# Dual_Serial_Card_V2.net
KiCad netlist of a schematic drawn in EAGLE
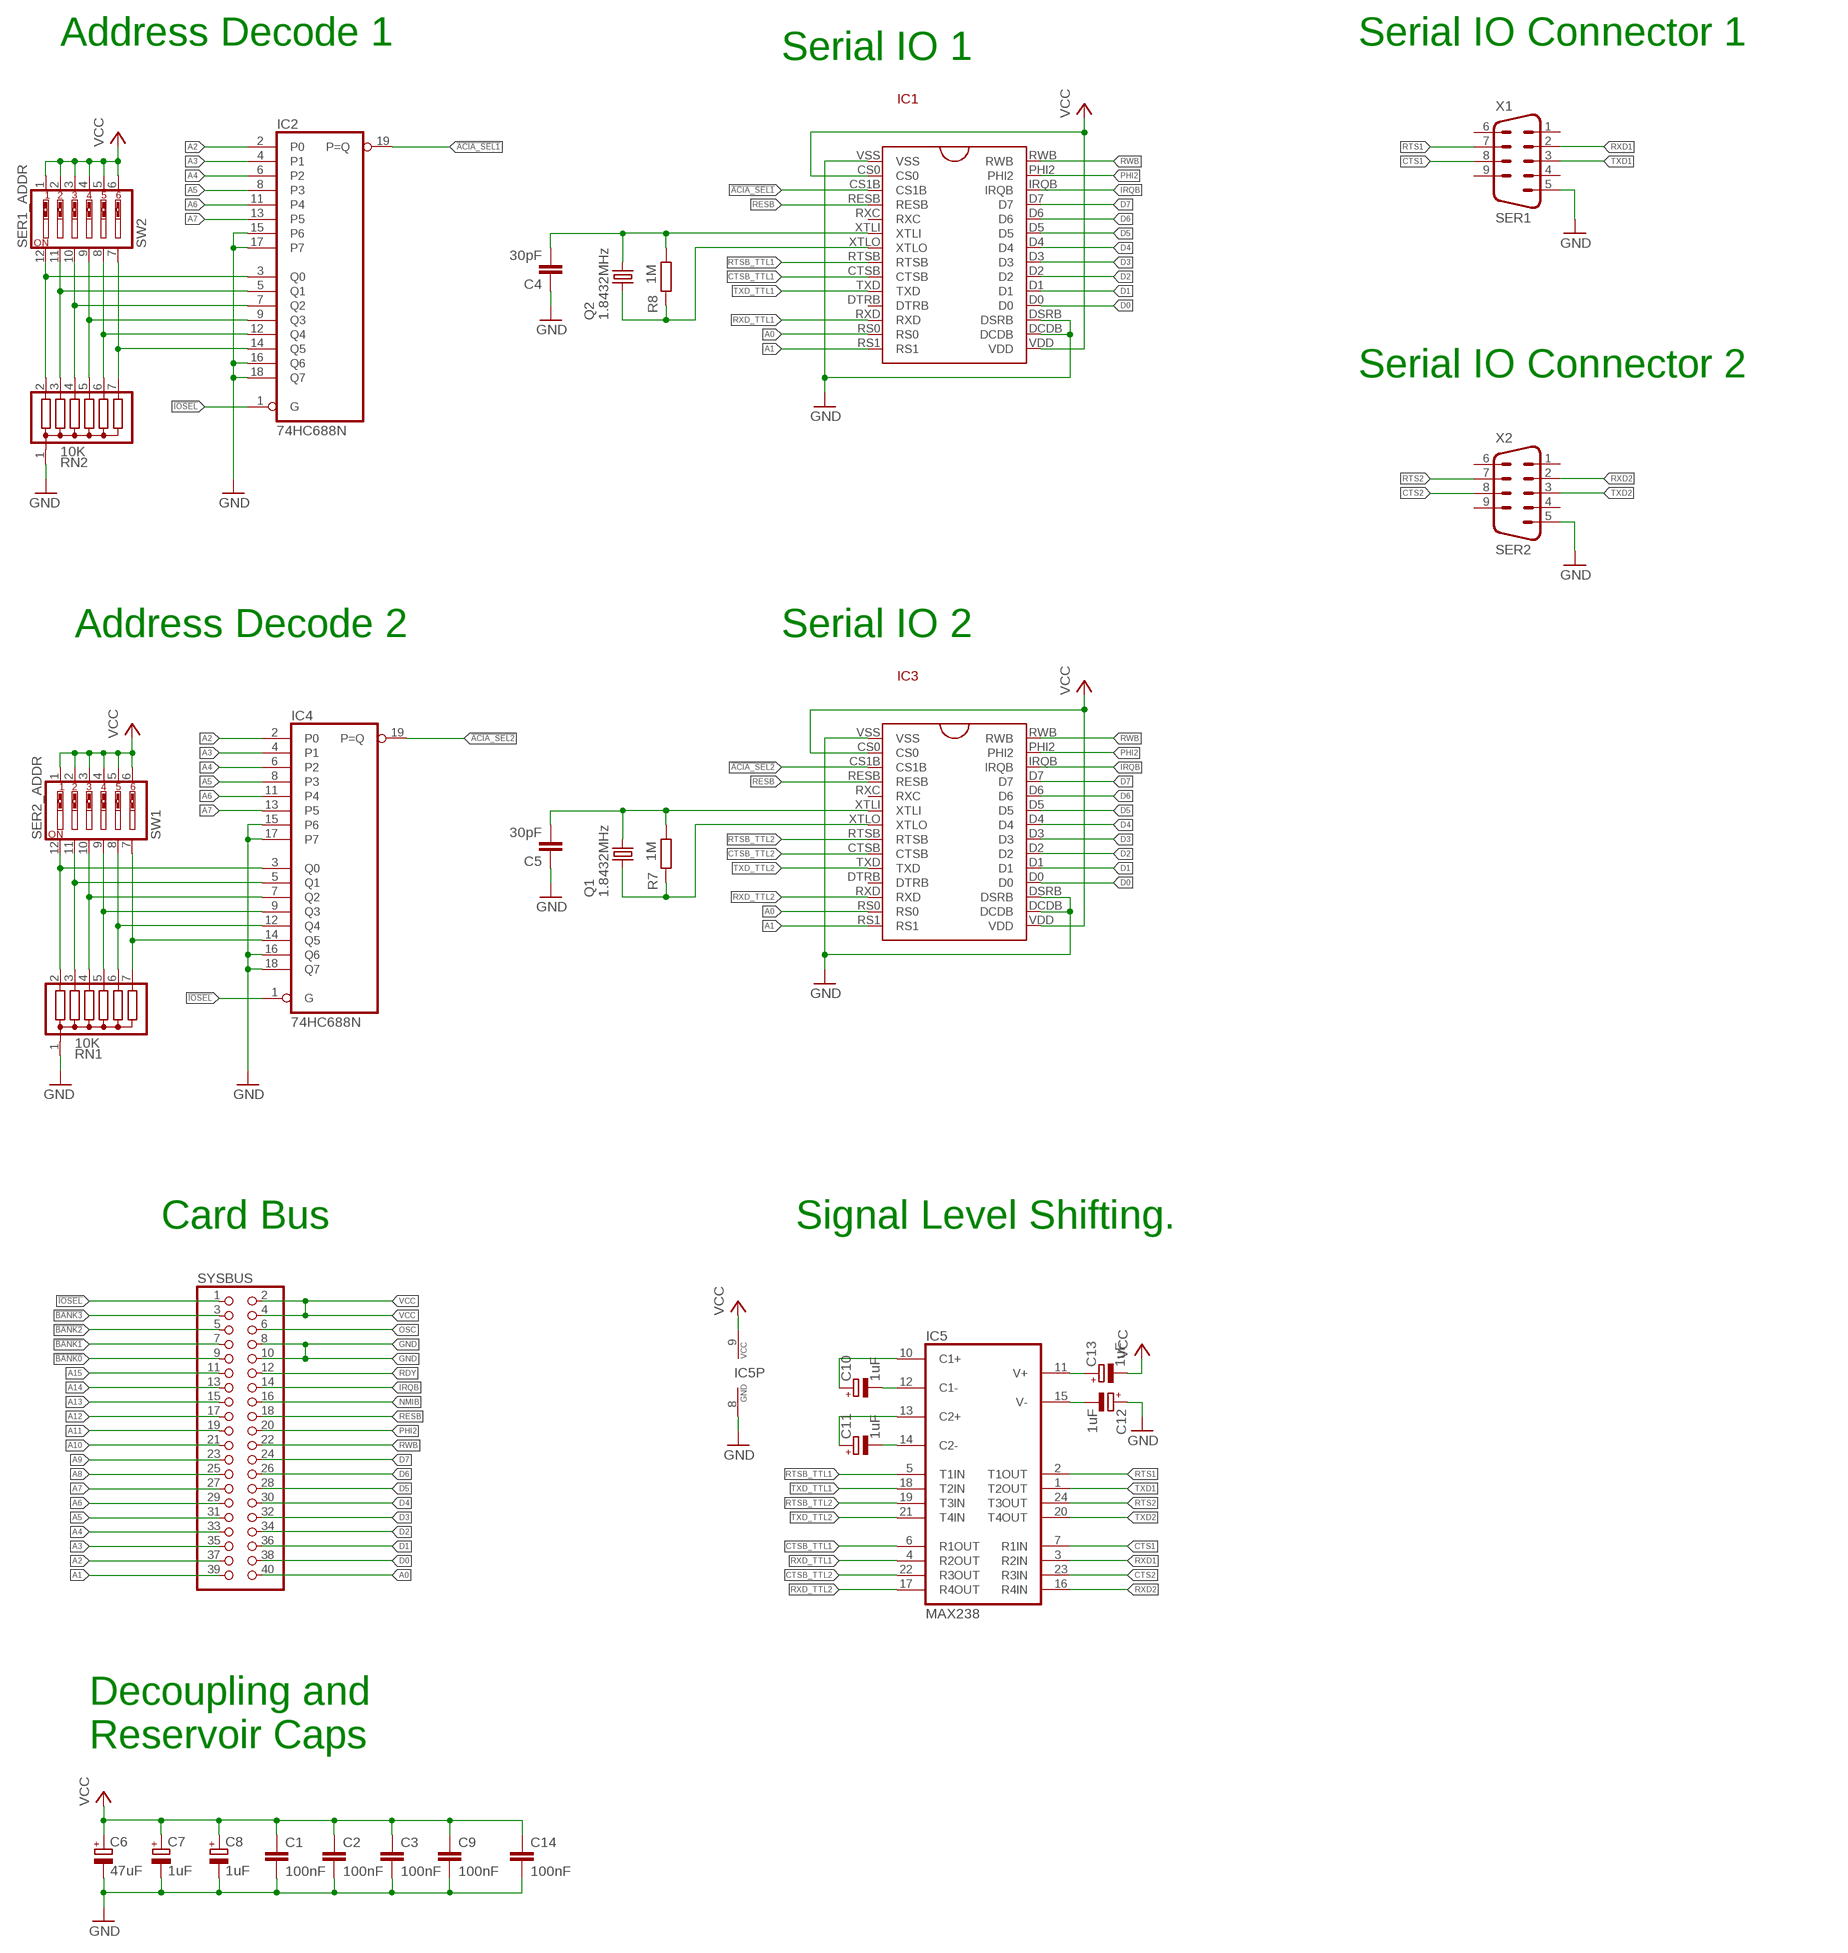
[diagram p0: schematic, sheet 1]

(export (version "E")
  (design (tool "Eeschema 10.0.6"))
  (components
    (comp (ref "C1")
      (value "100nF")
      (footprint "eagle-import:C025-025X050")
      (libsource (lib "eagle-import") (part "C-EU025-025X050"))
    )
    (comp (ref "C2")
      (value "100nF")
      (footprint "eagle-import:C025-025X050")
      (libsource (lib "eagle-import") (part "C-EU025-025X050"))
    )
    (comp (ref "C3")
      (value "100nF")
      (footprint "eagle-import:C025-025X050")
      (libsource (lib "eagle-import") (part "C-EU025-025X050"))
    )
    (comp (ref "C4")
      (value "30pF")
      (footprint "eagle-import:C050-025X075")
      (libsource (lib "eagle-import") (part "C-EU050-025X075"))
    )
    (comp (ref "C5")
      (value "30pF")
      (footprint "eagle-import:C050-025X075")
      (libsource (lib "eagle-import") (part "C-EU050-025X075"))
    )
    (comp (ref "C6")
      (value "47uF")
      (footprint "eagle-import:E2,5-7")
      (libsource (lib "eagle-import") (part "CPOL-EUE2.5-7"))
    )
    (comp (ref "C7")
      (value "1uF")
      (footprint "eagle-import:E2,5-5")
      (libsource (lib "eagle-import") (part "CPOL-EUE2.5-5"))
    )
    (comp (ref "C8")
      (value "1uF")
      (footprint "eagle-import:E2,5-5")
      (libsource (lib "eagle-import") (part "CPOL-EUE2.5-5"))
    )
    (comp (ref "C9")
      (value "100nF")
      (footprint "eagle-import:C025-025X050")
      (libsource (lib "eagle-import") (part "C-EU025-025X050"))
    )
    (comp (ref "C10")
      (value "1uF")
      (footprint "eagle-import:E2,5-5")
      (libsource (lib "eagle-import") (part "CPOL-EUE2.5-5"))
    )
    (comp (ref "C11")
      (value "1uF")
      (footprint "eagle-import:E2,5-5")
      (libsource (lib "eagle-import") (part "CPOL-EUE2.5-5"))
    )
    (comp (ref "C12")
      (value "1uF")
      (footprint "eagle-import:E2,5-5")
      (libsource (lib "eagle-import") (part "CPOL-EUE2.5-5"))
    )
    (comp (ref "C13")
      (value "1uF")
      (footprint "eagle-import:E2,5-5")
      (libsource (lib "eagle-import") (part "CPOL-EUE2.5-5"))
    )
    (comp (ref "C14")
      (value "100nF")
      (footprint "eagle-import:C025-025X050")
      (libsource (lib "eagle-import") (part "C-EU025-025X050"))
    )
    (comp (ref "IC1")
      (value "W65C51N-DIP")
      (footprint "eagle-import:W65C51N-DIP")
      (libsource (lib "eagle-import") (part "W65C51N-DIP"))
    )
    (comp (ref "IC2")
      (value "74HC688N")
      (footprint "eagle-import:DIL20")
      (libsource (lib "eagle-import") (part "74688NHC"))
    )
    (comp (ref "IC3")
      (value "W65C51N-DIP")
      (footprint "eagle-import:W65C51N-DIP")
      (libsource (lib "eagle-import") (part "W65C51N-DIP"))
    )
    (comp (ref "IC4")
      (value "74HC688N")
      (footprint "eagle-import:DIL20")
      (libsource (lib "eagle-import") (part "74688NHC"))
    )
    (comp (ref "IC5")
      (value "MAX238")
      (footprint "eagle-import:DIL24-3")
      (libsource (lib "eagle-import") (part "MAX238"))
    )
    (comp (ref "Q1")
      (value "1.8432MHz")
      (footprint "eagle-import:HC49_S")
      (libsource (lib "eagle-import") (part "CRYSTALHC49S"))
    )
    (comp (ref "Q2")
      (value "1.8432MHz")
      (footprint "eagle-import:HC49_S")
      (libsource (lib "eagle-import") (part "CRYSTALHC49S"))
    )
    (comp (ref "R7")
      (value "1M")
      (footprint "eagle-import:0207_2V")
      (libsource (lib "eagle-import") (part "R-EU_0207/2V"))
    )
    (comp (ref "R8")
      (value "1M")
      (footprint "eagle-import:0207_2V")
      (libsource (lib "eagle-import") (part "R-EU_0207/2V"))
    )
    (comp (ref "RN1")
      (value "10K")
      (footprint "eagle-import:SIL7")
      (libsource (lib "eagle-import") (part "G06R"))
    )
    (comp (ref "RN2")
      (value "10K")
      (footprint "eagle-import:SIL7")
      (libsource (lib "eagle-import") (part "G06R"))
    )
    (comp (ref "SW1")
      (value "SER2_ADDR")
      (footprint "eagle-import:EDG-06")
      (libsource (lib "eagle-import") (part "SW_DIP-6"))
    )
    (comp (ref "SW2")
      (value "SER1_ADDR")
      (footprint "eagle-import:EDG-06")
      (libsource (lib "eagle-import") (part "SW_DIP-6"))
    )
    (comp (ref "SYSBUS")
      (value "PINHD-2X20/90")
      (footprint "eagle-import:2X20_90")
      (libsource (lib "eagle-import") (part "PINHD-2X20/90"))
    )
    (comp (ref "X1")
      (value "SER1")
      (footprint "eagle-import:M09HP")
      (libsource (lib "eagle-import") (part "M09HP"))
    )
    (comp (ref "X2")
      (value "SER2")
      (footprint "eagle-import:M09HP")
      (libsource (lib "eagle-import") (part "M09HP"))
    )
  )
  (nets
    (net (code "1") (name "/~{ACIA_SEL1}") (class "Default")
      (node (ref "IC1") (pin "CS1B") (pinfunction "CS1B_CS1B") (pintype "input"))
      (node (ref "IC2") (pin "19") (pinfunction "P=Q_19") (pintype "output"))
    )
    (net (code "2") (name "/~{ACIA_SEL2}") (class "Default")
      (node (ref "IC3") (pin "CS1B") (pinfunction "CS1B_CS1B") (pintype "input"))
      (node (ref "IC4") (pin "19") (pinfunction "P=Q_19") (pintype "output"))
    )
    (net (code "3") (name "/~{BANK0}") (class "Default")
      (node (ref "SYSBUS") (pin "9") (pinfunction "9_9") (pintype "passive"))
    )
    (net (code "4") (name "/~{BANK1}") (class "Default")
      (node (ref "SYSBUS") (pin "7") (pinfunction "7_7") (pintype "passive"))
    )
    (net (code "5") (name "/~{BANK2}") (class "Default")
      (node (ref "SYSBUS") (pin "5") (pinfunction "5_5") (pintype "passive"))
    )
    (net (code "6") (name "/~{BANK3}") (class "Default")
      (node (ref "SYSBUS") (pin "3") (pinfunction "3_3") (pintype "passive"))
    )
    (net (code "7") (name "/~{IOSEL}") (class "Default")
      (node (ref "IC2") (pin "1") (pinfunction "G_1") (pintype "input"))
      (node (ref "IC4") (pin "1") (pinfunction "G_1") (pintype "input"))
      (node (ref "SYSBUS") (pin "1") (pinfunction "1_1") (pintype "passive"))
    )
    (net (code "8") (name "A0") (class "Default")
      (node (ref "IC1") (pin "RS0") (pinfunction "RS0_RS0") (pintype "input"))
      (node (ref "IC3") (pin "RS0") (pinfunction "RS0_RS0") (pintype "input"))
      (node (ref "SYSBUS") (pin "40") (pinfunction "40_40") (pintype "passive"))
    )
    (net (code "9") (name "A1") (class "Default")
      (node (ref "IC1") (pin "RS1") (pinfunction "RS1_RS1") (pintype "input"))
      (node (ref "IC3") (pin "RS1") (pinfunction "RS1_RS1") (pintype "input"))
      (node (ref "SYSBUS") (pin "39") (pinfunction "39_39") (pintype "passive"))
    )
    (net (code "10") (name "A2") (class "Default")
      (node (ref "IC2") (pin "2") (pinfunction "P0_2") (pintype "input"))
      (node (ref "IC4") (pin "2") (pinfunction "P0_2") (pintype "input"))
      (node (ref "SYSBUS") (pin "37") (pinfunction "37_37") (pintype "passive"))
    )
    (net (code "11") (name "A3") (class "Default")
      (node (ref "IC2") (pin "4") (pinfunction "P1_4") (pintype "input"))
      (node (ref "IC4") (pin "4") (pinfunction "P1_4") (pintype "input"))
      (node (ref "SYSBUS") (pin "35") (pinfunction "35_35") (pintype "passive"))
    )
    (net (code "12") (name "A4") (class "Default")
      (node (ref "IC2") (pin "6") (pinfunction "P2_6") (pintype "input"))
      (node (ref "IC4") (pin "6") (pinfunction "P2_6") (pintype "input"))
      (node (ref "SYSBUS") (pin "33") (pinfunction "33_33") (pintype "passive"))
    )
    (net (code "13") (name "A5") (class "Default")
      (node (ref "IC2") (pin "8") (pinfunction "P3_8") (pintype "input"))
      (node (ref "IC4") (pin "8") (pinfunction "P3_8") (pintype "input"))
      (node (ref "SYSBUS") (pin "31") (pinfunction "31_31") (pintype "passive"))
    )
    (net (code "14") (name "A6") (class "Default")
      (node (ref "IC2") (pin "11") (pinfunction "P4_11") (pintype "input"))
      (node (ref "IC4") (pin "11") (pinfunction "P4_11") (pintype "input"))
      (node (ref "SYSBUS") (pin "29") (pinfunction "29_29") (pintype "passive"))
    )
    (net (code "15") (name "A7") (class "Default")
      (node (ref "IC2") (pin "13") (pinfunction "P5_13") (pintype "input"))
      (node (ref "IC4") (pin "13") (pinfunction "P5_13") (pintype "input"))
      (node (ref "SYSBUS") (pin "27") (pinfunction "27_27") (pintype "passive"))
    )
    (net (code "16") (name "A8") (class "Default")
      (node (ref "SYSBUS") (pin "25") (pinfunction "25_25") (pintype "passive"))
    )
    (net (code "17") (name "A9") (class "Default")
      (node (ref "SYSBUS") (pin "23") (pinfunction "23_23") (pintype "passive"))
    )
    (net (code "18") (name "A10") (class "Default")
      (node (ref "SYSBUS") (pin "21") (pinfunction "21_21") (pintype "passive"))
    )
    (net (code "19") (name "A11") (class "Default")
      (node (ref "SYSBUS") (pin "19") (pinfunction "19_19") (pintype "passive"))
    )
    (net (code "20") (name "A12") (class "Default")
      (node (ref "SYSBUS") (pin "17") (pinfunction "17_17") (pintype "passive"))
    )
    (net (code "21") (name "A13") (class "Default")
      (node (ref "SYSBUS") (pin "15") (pinfunction "15_15") (pintype "passive"))
    )
    (net (code "22") (name "A14") (class "Default")
      (node (ref "SYSBUS") (pin "13") (pinfunction "13_13") (pintype "passive"))
    )
    (net (code "23") (name "A15") (class "Default")
      (node (ref "SYSBUS") (pin "11") (pinfunction "11_11") (pintype "passive"))
    )
    (net (code "24") (name "CTS1") (class "Default")
      (node (ref "IC5") (pin "7") (pinfunction "R1IN_7") (pintype "input"))
      (node (ref "X1") (pin "8") (pinfunction "8_8") (pintype "passive"))
    )
    (net (code "25") (name "CTS2") (class "Default")
      (node (ref "IC5") (pin "23") (pinfunction "R3IN_23") (pintype "input"))
      (node (ref "X2") (pin "8") (pinfunction "8_8") (pintype "passive"))
    )
    (net (code "26") (name "CTSB_TTL1") (class "Default")
      (node (ref "IC1") (pin "CTSB") (pinfunction "CTSB_CTSB") (pintype "input"))
      (node (ref "IC5") (pin "6") (pinfunction "R1OUT_6") (pintype "output"))
    )
    (net (code "27") (name "CTSB_TTL2") (class "Default")
      (node (ref "IC3") (pin "CTSB") (pinfunction "CTSB_CTSB") (pintype "input"))
      (node (ref "IC5") (pin "22") (pinfunction "R3OUT_22") (pintype "output"))
    )
    (net (code "28") (name "D0") (class "Default")
      (node (ref "IC1") (pin "D0") (pinfunction "D0_D0") (pintype "bidirectional"))
      (node (ref "IC3") (pin "D0") (pinfunction "D0_D0") (pintype "bidirectional"))
      (node (ref "SYSBUS") (pin "38") (pinfunction "38_38") (pintype "passive"))
    )
    (net (code "29") (name "D1") (class "Default")
      (node (ref "IC1") (pin "D1") (pinfunction "D1_D1") (pintype "bidirectional"))
      (node (ref "IC3") (pin "D1") (pinfunction "D1_D1") (pintype "bidirectional"))
      (node (ref "SYSBUS") (pin "36") (pinfunction "36_36") (pintype "passive"))
    )
    (net (code "30") (name "D2") (class "Default")
      (node (ref "IC1") (pin "D2") (pinfunction "D2_D2") (pintype "bidirectional"))
      (node (ref "IC3") (pin "D2") (pinfunction "D2_D2") (pintype "bidirectional"))
      (node (ref "SYSBUS") (pin "34") (pinfunction "34_34") (pintype "passive"))
    )
    (net (code "31") (name "D3") (class "Default")
      (node (ref "IC1") (pin "D3") (pinfunction "D3_D3") (pintype "bidirectional"))
      (node (ref "IC3") (pin "D3") (pinfunction "D3_D3") (pintype "bidirectional"))
      (node (ref "SYSBUS") (pin "32") (pinfunction "32_32") (pintype "passive"))
    )
    (net (code "32") (name "D4") (class "Default")
      (node (ref "IC1") (pin "D4") (pinfunction "D4_D4") (pintype "bidirectional"))
      (node (ref "IC3") (pin "D4") (pinfunction "D4_D4") (pintype "bidirectional"))
      (node (ref "SYSBUS") (pin "30") (pinfunction "30_30") (pintype "passive"))
    )
    (net (code "33") (name "D5") (class "Default")
      (node (ref "IC1") (pin "D5") (pinfunction "D5_D5") (pintype "bidirectional"))
      (node (ref "IC3") (pin "D5") (pinfunction "D5_D5") (pintype "bidirectional"))
      (node (ref "SYSBUS") (pin "28") (pinfunction "28_28") (pintype "passive"))
    )
    (net (code "34") (name "D6") (class "Default")
      (node (ref "IC1") (pin "D6") (pinfunction "D6_D6") (pintype "bidirectional"))
      (node (ref "IC3") (pin "D6") (pinfunction "D6_D6") (pintype "bidirectional"))
      (node (ref "SYSBUS") (pin "26") (pinfunction "26_26") (pintype "passive"))
    )
    (net (code "35") (name "D7") (class "Default")
      (node (ref "IC1") (pin "D7") (pinfunction "D7_D7") (pintype "bidirectional"))
      (node (ref "IC3") (pin "D7") (pinfunction "D7_D7") (pintype "bidirectional"))
      (node (ref "SYSBUS") (pin "24") (pinfunction "24_24") (pintype "passive"))
    )
    (net (code "36") (name "GND") (class "Default")
      (node (ref "C1") (pin "2") (pinfunction "2_2") (pintype "passive"))
      (node (ref "C12") (pin "+") (pinfunction "+_+") (pintype "passive"))
      (node (ref "C14") (pin "2") (pinfunction "2_2") (pintype "passive"))
      (node (ref "C2") (pin "2") (pinfunction "2_2") (pintype "passive"))
      (node (ref "C3") (pin "2") (pinfunction "2_2") (pintype "passive"))
      (node (ref "C4") (pin "1") (pinfunction "1_1") (pintype "passive"))
      (node (ref "C5") (pin "1") (pinfunction "1_1") (pintype "passive"))
      (node (ref "C6") (pin "-") (pinfunction "-_-") (pintype "passive"))
      (node (ref "C7") (pin "-") (pinfunction "-_-") (pintype "passive"))
      (node (ref "C8") (pin "-") (pinfunction "-_-") (pintype "passive"))
      (node (ref "C9") (pin "2") (pinfunction "2_2") (pintype "passive"))
      (node (ref "IC1") (pin "DCDB") (pinfunction "DCDB_DCDB") (pintype "input"))
      (node (ref "IC1") (pin "DSRB") (pinfunction "DSRB_DSRB") (pintype "input"))
      (node (ref "IC1") (pin "VSS") (pinfunction "VSS_VSS") (pintype "power_in"))
      (node (ref "IC2") (pin "15") (pinfunction "P6_15") (pintype "input"))
      (node (ref "IC2") (pin "16") (pinfunction "Q6_16") (pintype "input"))
      (node (ref "IC2") (pin "17") (pinfunction "P7_17") (pintype "input"))
      (node (ref "IC2") (pin "18") (pinfunction "Q7_18") (pintype "input"))
      (node (ref "IC3") (pin "DCDB") (pinfunction "DCDB_DCDB") (pintype "input"))
      (node (ref "IC3") (pin "DSRB") (pinfunction "DSRB_DSRB") (pintype "input"))
      (node (ref "IC3") (pin "VSS") (pinfunction "VSS_VSS") (pintype "power_in"))
      (node (ref "IC4") (pin "15") (pinfunction "P6_15") (pintype "input"))
      (node (ref "IC4") (pin "16") (pinfunction "Q6_16") (pintype "input"))
      (node (ref "IC4") (pin "17") (pinfunction "P7_17") (pintype "input"))
      (node (ref "IC4") (pin "18") (pinfunction "Q7_18") (pintype "input"))
      (node (ref "IC5") (pin "8") (pinfunction "GND_8") (pintype "power_in"))
      (node (ref "RN1") (pin "1") (pinfunction "1_1") (pintype "passive"))
      (node (ref "RN2") (pin "1") (pinfunction "1_1") (pintype "passive"))
      (node (ref "SYSBUS") (pin "10") (pinfunction "10_10") (pintype "passive"))
      (node (ref "SYSBUS") (pin "8") (pinfunction "8_8") (pintype "passive"))
      (node (ref "X1") (pin "5") (pinfunction "5_5") (pintype "passive"))
      (node (ref "X2") (pin "5") (pinfunction "5_5") (pintype "passive"))
    )
    (net (code "37") (name "IRQB") (class "Default")
      (node (ref "IC1") (pin "IRQB") (pinfunction "IRQB_IRQB") (pintype "output"))
      (node (ref "IC3") (pin "IRQB") (pinfunction "IRQB_IRQB") (pintype "output"))
      (node (ref "SYSBUS") (pin "14") (pinfunction "14_14") (pintype "passive"))
    )
    (net (code "38") (name "NMIB") (class "Default")
      (node (ref "SYSBUS") (pin "16") (pinfunction "16_16") (pintype "passive"))
    )
    (net (code "39") (name "Net-(C4-Pad2)") (class "Default")
      (node (ref "C4") (pin "2") (pinfunction "2_2") (pintype "passive"))
      (node (ref "IC1") (pin "XTLI") (pinfunction "XTLI_XTLI") (pintype "input"))
      (node (ref "Q2") (pin "2") (pinfunction "2_2") (pintype "passive"))
      (node (ref "R8") (pin "2") (pinfunction "2_2") (pintype "passive"))
    )
    (net (code "40") (name "Net-(C5-Pad2)") (class "Default")
      (node (ref "C5") (pin "2") (pinfunction "2_2") (pintype "passive"))
      (node (ref "IC3") (pin "XTLI") (pinfunction "XTLI_XTLI") (pintype "input"))
      (node (ref "Q1") (pin "2") (pinfunction "2_2") (pintype "passive"))
      (node (ref "R7") (pin "2") (pinfunction "2_2") (pintype "passive"))
    )
    (net (code "41") (name "Net-(IC1-PadXTLO)") (class "Default")
      (node (ref "IC1") (pin "XTLO") (pinfunction "XTLO_XTLO") (pintype "output"))
      (node (ref "Q2") (pin "1") (pinfunction "1_1") (pintype "passive"))
      (node (ref "R8") (pin "1") (pinfunction "1_1") (pintype "passive"))
    )
    (net (code "42") (name "Net-(IC2A-Q0)") (class "Default")
      (node (ref "IC2") (pin "3") (pinfunction "Q0_3") (pintype "input"))
      (node (ref "RN2") (pin "2") (pinfunction "2_2") (pintype "passive"))
      (node (ref "SW2") (pin "12") (pinfunction "12_12") (pintype "passive"))
    )
    (net (code "43") (name "Net-(IC2A-Q1)") (class "Default")
      (node (ref "IC2") (pin "5") (pinfunction "Q1_5") (pintype "input"))
      (node (ref "RN2") (pin "3") (pinfunction "3_3") (pintype "passive"))
      (node (ref "SW2") (pin "11") (pinfunction "11_11") (pintype "passive"))
    )
    (net (code "44") (name "Net-(IC2A-Q2)") (class "Default")
      (node (ref "IC2") (pin "7") (pinfunction "Q2_7") (pintype "input"))
      (node (ref "RN2") (pin "4") (pinfunction "4_4") (pintype "passive"))
      (node (ref "SW2") (pin "10") (pinfunction "10_10") (pintype "passive"))
    )
    (net (code "45") (name "Net-(IC2A-Q3)") (class "Default")
      (node (ref "IC2") (pin "9") (pinfunction "Q3_9") (pintype "input"))
      (node (ref "RN2") (pin "5") (pinfunction "5_5") (pintype "passive"))
      (node (ref "SW2") (pin "9") (pinfunction "9_9") (pintype "passive"))
    )
    (net (code "46") (name "Net-(IC2A-Q4)") (class "Default")
      (node (ref "IC2") (pin "12") (pinfunction "Q4_12") (pintype "input"))
      (node (ref "RN2") (pin "6") (pinfunction "6_6") (pintype "passive"))
      (node (ref "SW2") (pin "8") (pinfunction "8_8") (pintype "passive"))
    )
    (net (code "47") (name "Net-(IC2A-Q5)") (class "Default")
      (node (ref "IC2") (pin "14") (pinfunction "Q5_14") (pintype "input"))
      (node (ref "RN2") (pin "7") (pinfunction "7_7") (pintype "passive"))
      (node (ref "SW2") (pin "7") (pinfunction "7_7") (pintype "passive"))
    )
    (net (code "48") (name "Net-(IC3-PadXTLO)") (class "Default")
      (node (ref "IC3") (pin "XTLO") (pinfunction "XTLO_XTLO") (pintype "output"))
      (node (ref "Q1") (pin "1") (pinfunction "1_1") (pintype "passive"))
      (node (ref "R7") (pin "1") (pinfunction "1_1") (pintype "passive"))
    )
    (net (code "49") (name "Net-(IC4A-Q0)") (class "Default")
      (node (ref "IC4") (pin "3") (pinfunction "Q0_3") (pintype "input"))
      (node (ref "RN1") (pin "2") (pinfunction "2_2") (pintype "passive"))
      (node (ref "SW1") (pin "12") (pinfunction "12_12") (pintype "passive"))
    )
    (net (code "50") (name "Net-(IC4A-Q1)") (class "Default")
      (node (ref "IC4") (pin "5") (pinfunction "Q1_5") (pintype "input"))
      (node (ref "RN1") (pin "3") (pinfunction "3_3") (pintype "passive"))
      (node (ref "SW1") (pin "11") (pinfunction "11_11") (pintype "passive"))
    )
    (net (code "51") (name "Net-(IC4A-Q2)") (class "Default")
      (node (ref "IC4") (pin "7") (pinfunction "Q2_7") (pintype "input"))
      (node (ref "RN1") (pin "4") (pinfunction "4_4") (pintype "passive"))
      (node (ref "SW1") (pin "10") (pinfunction "10_10") (pintype "passive"))
    )
    (net (code "52") (name "Net-(IC4A-Q3)") (class "Default")
      (node (ref "IC4") (pin "9") (pinfunction "Q3_9") (pintype "input"))
      (node (ref "RN1") (pin "5") (pinfunction "5_5") (pintype "passive"))
      (node (ref "SW1") (pin "9") (pinfunction "9_9") (pintype "passive"))
    )
    (net (code "53") (name "Net-(IC4A-Q4)") (class "Default")
      (node (ref "IC4") (pin "12") (pinfunction "Q4_12") (pintype "input"))
      (node (ref "RN1") (pin "6") (pinfunction "6_6") (pintype "passive"))
      (node (ref "SW1") (pin "8") (pinfunction "8_8") (pintype "passive"))
    )
    (net (code "54") (name "Net-(IC4A-Q5)") (class "Default")
      (node (ref "IC4") (pin "14") (pinfunction "Q5_14") (pintype "input"))
      (node (ref "RN1") (pin "7") (pinfunction "7_7") (pintype "passive"))
      (node (ref "SW1") (pin "7") (pinfunction "7_7") (pintype "passive"))
    )
    (net (code "55") (name "Net-(IC5A-C1+)") (class "Default")
      (node (ref "C10") (pin "+") (pinfunction "+_+") (pintype "passive"))
      (node (ref "IC5") (pin "10") (pinfunction "C1+_10") (pintype "bidirectional"))
    )
    (net (code "56") (name "Net-(IC5A-C1-)") (class "Default")
      (node (ref "C10") (pin "-") (pinfunction "-_-") (pintype "passive"))
      (node (ref "IC5") (pin "12") (pinfunction "C1-_12") (pintype "bidirectional"))
    )
    (net (code "57") (name "Net-(IC5A-C2+)") (class "Default")
      (node (ref "C11") (pin "+") (pinfunction "+_+") (pintype "passive"))
      (node (ref "IC5") (pin "13") (pinfunction "C2+_13") (pintype "bidirectional"))
    )
    (net (code "58") (name "Net-(IC5A-C2-)") (class "Default")
      (node (ref "C11") (pin "-") (pinfunction "-_-") (pintype "passive"))
      (node (ref "IC5") (pin "14") (pinfunction "C2-_14") (pintype "bidirectional"))
    )
    (net (code "59") (name "Net-(IC5A-V+)") (class "Default")
      (node (ref "C13") (pin "+") (pinfunction "+_+") (pintype "passive"))
      (node (ref "IC5") (pin "11") (pinfunction "V+_11") (pintype "bidirectional"))
    )
    (net (code "60") (name "Net-(IC5A-V-)") (class "Default")
      (node (ref "C12") (pin "-") (pinfunction "-_-") (pintype "passive"))
      (node (ref "IC5") (pin "15") (pinfunction "V-_15") (pintype "bidirectional"))
    )
    (net (code "61") (name "OSC") (class "Default")
      (node (ref "SYSBUS") (pin "6") (pinfunction "6_6") (pintype "passive"))
    )
    (net (code "62") (name "PHI2") (class "Default")
      (node (ref "IC1") (pin "PHI2") (pinfunction "PHI2_PHI2") (pintype "input"))
      (node (ref "IC3") (pin "PHI2") (pinfunction "PHI2_PHI2") (pintype "input"))
      (node (ref "SYSBUS") (pin "20") (pinfunction "20_20") (pintype "passive"))
    )
    (net (code "63") (name "RDY") (class "Default")
      (node (ref "SYSBUS") (pin "12") (pinfunction "12_12") (pintype "passive"))
    )
    (net (code "64") (name "RESB") (class "Default")
      (node (ref "IC1") (pin "RESB") (pinfunction "RESB_RESB") (pintype "input"))
      (node (ref "IC3") (pin "RESB") (pinfunction "RESB_RESB") (pintype "input"))
      (node (ref "SYSBUS") (pin "18") (pinfunction "18_18") (pintype "passive"))
    )
    (net (code "65") (name "RTS1") (class "Default")
      (node (ref "IC5") (pin "2") (pinfunction "T1OUT_2") (pintype "output"))
      (node (ref "X1") (pin "7") (pinfunction "7_7") (pintype "passive"))
    )
    (net (code "66") (name "RTS2") (class "Default")
      (node (ref "IC5") (pin "24") (pinfunction "T3OUT_24") (pintype "output"))
      (node (ref "X2") (pin "7") (pinfunction "7_7") (pintype "passive"))
    )
    (net (code "67") (name "RTSB_TTL1") (class "Default")
      (node (ref "IC1") (pin "RTSB") (pinfunction "RTSB_RTSB") (pintype "output"))
      (node (ref "IC5") (pin "5") (pinfunction "T1IN_5") (pintype "input"))
    )
    (net (code "68") (name "RTSB_TTL2") (class "Default")
      (node (ref "IC3") (pin "RTSB") (pinfunction "RTSB_RTSB") (pintype "output"))
      (node (ref "IC5") (pin "19") (pinfunction "T3IN_19") (pintype "input"))
    )
    (net (code "69") (name "RWB") (class "Default")
      (node (ref "IC1") (pin "RWB") (pinfunction "RWB_RWB") (pintype "input"))
      (node (ref "IC3") (pin "RWB") (pinfunction "RWB_RWB") (pintype "input"))
      (node (ref "SYSBUS") (pin "22") (pinfunction "22_22") (pintype "passive"))
    )
    (net (code "70") (name "RXD1") (class "Default")
      (node (ref "IC5") (pin "3") (pinfunction "R2IN_3") (pintype "input"))
      (node (ref "X1") (pin "2") (pinfunction "2_2") (pintype "passive"))
    )
    (net (code "71") (name "RXD2") (class "Default")
      (node (ref "IC5") (pin "16") (pinfunction "R4IN_16") (pintype "input"))
      (node (ref "X2") (pin "2") (pinfunction "2_2") (pintype "passive"))
    )
    (net (code "72") (name "RXD_TTL1") (class "Default")
      (node (ref "IC1") (pin "RXD") (pinfunction "RXD_RXD") (pintype "input"))
      (node (ref "IC5") (pin "4") (pinfunction "R2OUT_4") (pintype "output"))
    )
    (net (code "73") (name "RXD_TTL2") (class "Default")
      (node (ref "IC3") (pin "RXD") (pinfunction "RXD_RXD") (pintype "input"))
      (node (ref "IC5") (pin "17") (pinfunction "R4OUT_17") (pintype "output"))
    )
    (net (code "74") (name "TXD1") (class "Default")
      (node (ref "IC5") (pin "1") (pinfunction "T2OUT_1") (pintype "output"))
      (node (ref "X1") (pin "3") (pinfunction "3_3") (pintype "passive"))
    )
    (net (code "75") (name "TXD2") (class "Default")
      (node (ref "IC5") (pin "20") (pinfunction "T4OUT_20") (pintype "output"))
      (node (ref "X2") (pin "3") (pinfunction "3_3") (pintype "passive"))
    )
    (net (code "76") (name "TXD_TTL1") (class "Default")
      (node (ref "IC1") (pin "TXD") (pinfunction "TXD_TXD") (pintype "output"))
      (node (ref "IC5") (pin "18") (pinfunction "T2IN_18") (pintype "input"))
    )
    (net (code "77") (name "TXD_TTL2") (class "Default")
      (node (ref "IC3") (pin "TXD") (pinfunction "TXD_TXD") (pintype "output"))
      (node (ref "IC5") (pin "21") (pinfunction "T4IN_21") (pintype "input"))
    )
    (net (code "78") (name "VCC") (class "Default")
      (node (ref "C1") (pin "1") (pinfunction "1_1") (pintype "passive"))
      (node (ref "C13") (pin "-") (pinfunction "-_-") (pintype "passive"))
      (node (ref "C14") (pin "1") (pinfunction "1_1") (pintype "passive"))
      (node (ref "C2") (pin "1") (pinfunction "1_1") (pintype "passive"))
      (node (ref "C3") (pin "1") (pinfunction "1_1") (pintype "passive"))
      (node (ref "C6") (pin "+") (pinfunction "+_+") (pintype "passive"))
      (node (ref "C7") (pin "+") (pinfunction "+_+") (pintype "passive"))
      (node (ref "C8") (pin "+") (pinfunction "+_+") (pintype "passive"))
      (node (ref "C9") (pin "1") (pinfunction "1_1") (pintype "passive"))
      (node (ref "IC1") (pin "CS0") (pinfunction "CS0_CS0") (pintype "input"))
      (node (ref "IC1") (pin "VDD") (pinfunction "VDD_VDD") (pintype "power_in"))
      (node (ref "IC3") (pin "CS0") (pinfunction "CS0_CS0") (pintype "input"))
      (node (ref "IC3") (pin "VDD") (pinfunction "VDD_VDD") (pintype "power_in"))
      (node (ref "IC5") (pin "9") (pinfunction "VCC_9") (pintype "power_in"))
      (node (ref "SW1") (pin "1") (pinfunction "1_1") (pintype "passive"))
      (node (ref "SW1") (pin "2") (pinfunction "2_2") (pintype "passive"))
      (node (ref "SW1") (pin "3") (pinfunction "3_3") (pintype "passive"))
      (node (ref "SW1") (pin "4") (pinfunction "4_4") (pintype "passive"))
      (node (ref "SW1") (pin "5") (pinfunction "5_5") (pintype "passive"))
      (node (ref "SW1") (pin "6") (pinfunction "6_6") (pintype "passive"))
      (node (ref "SW2") (pin "1") (pinfunction "1_1") (pintype "passive"))
      (node (ref "SW2") (pin "2") (pinfunction "2_2") (pintype "passive"))
      (node (ref "SW2") (pin "3") (pinfunction "3_3") (pintype "passive"))
      (node (ref "SW2") (pin "4") (pinfunction "4_4") (pintype "passive"))
      (node (ref "SW2") (pin "5") (pinfunction "5_5") (pintype "passive"))
      (node (ref "SW2") (pin "6") (pinfunction "6_6") (pintype "passive"))
      (node (ref "SYSBUS") (pin "2") (pinfunction "2_2") (pintype "passive"))
      (node (ref "SYSBUS") (pin "4") (pinfunction "4_4") (pintype "passive"))
    )
    (net (code "79") (name "unconnected-(IC1-PadDTRB)") (class "Default")
      (node (ref "IC1") (pin "DTRB") (pinfunction "DTRB_DTRB") (pintype "output"))
    )
    (net (code "80") (name "unconnected-(IC1-PadRXC)") (class "Default")
      (node (ref "IC1") (pin "RXC") (pinfunction "RXC_RXC") (pintype "bidirectional"))
    )
    (net (code "81") (name "unconnected-(IC3-PadDTRB)") (class "Default")
      (node (ref "IC3") (pin "DTRB") (pinfunction "DTRB_DTRB") (pintype "output"))
    )
    (net (code "82") (name "unconnected-(IC3-PadRXC)") (class "Default")
      (node (ref "IC3") (pin "RXC") (pinfunction "RXC_RXC") (pintype "bidirectional"))
    )
    (net (code "83") (name "unconnected-(X1-Pad1)") (class "Default")
      (node (ref "X1") (pin "1") (pinfunction "1_1") (pintype "passive"))
    )
    (net (code "84") (name "unconnected-(X1-Pad4)") (class "Default")
      (node (ref "X1") (pin "4") (pinfunction "4_4") (pintype "passive"))
    )
    (net (code "85") (name "unconnected-(X1-Pad6)") (class "Default")
      (node (ref "X1") (pin "6") (pinfunction "6_6") (pintype "passive"))
    )
    (net (code "86") (name "unconnected-(X1-Pad9)") (class "Default")
      (node (ref "X1") (pin "9") (pinfunction "9_9") (pintype "passive"))
    )
    (net (code "87") (name "unconnected-(X2-Pad1)") (class "Default")
      (node (ref "X2") (pin "1") (pinfunction "1_1") (pintype "passive"))
    )
    (net (code "88") (name "unconnected-(X2-Pad4)") (class "Default")
      (node (ref "X2") (pin "4") (pinfunction "4_4") (pintype "passive"))
    )
    (net (code "89") (name "unconnected-(X2-Pad6)") (class "Default")
      (node (ref "X2") (pin "6") (pinfunction "6_6") (pintype "passive"))
    )
    (net (code "90") (name "unconnected-(X2-Pad9)") (class "Default")
      (node (ref "X2") (pin "9") (pinfunction "9_9") (pintype "passive"))
    )
  )
)
